# STM32G071.net
KiCad netlist of a schematic drawn in Altium Designer
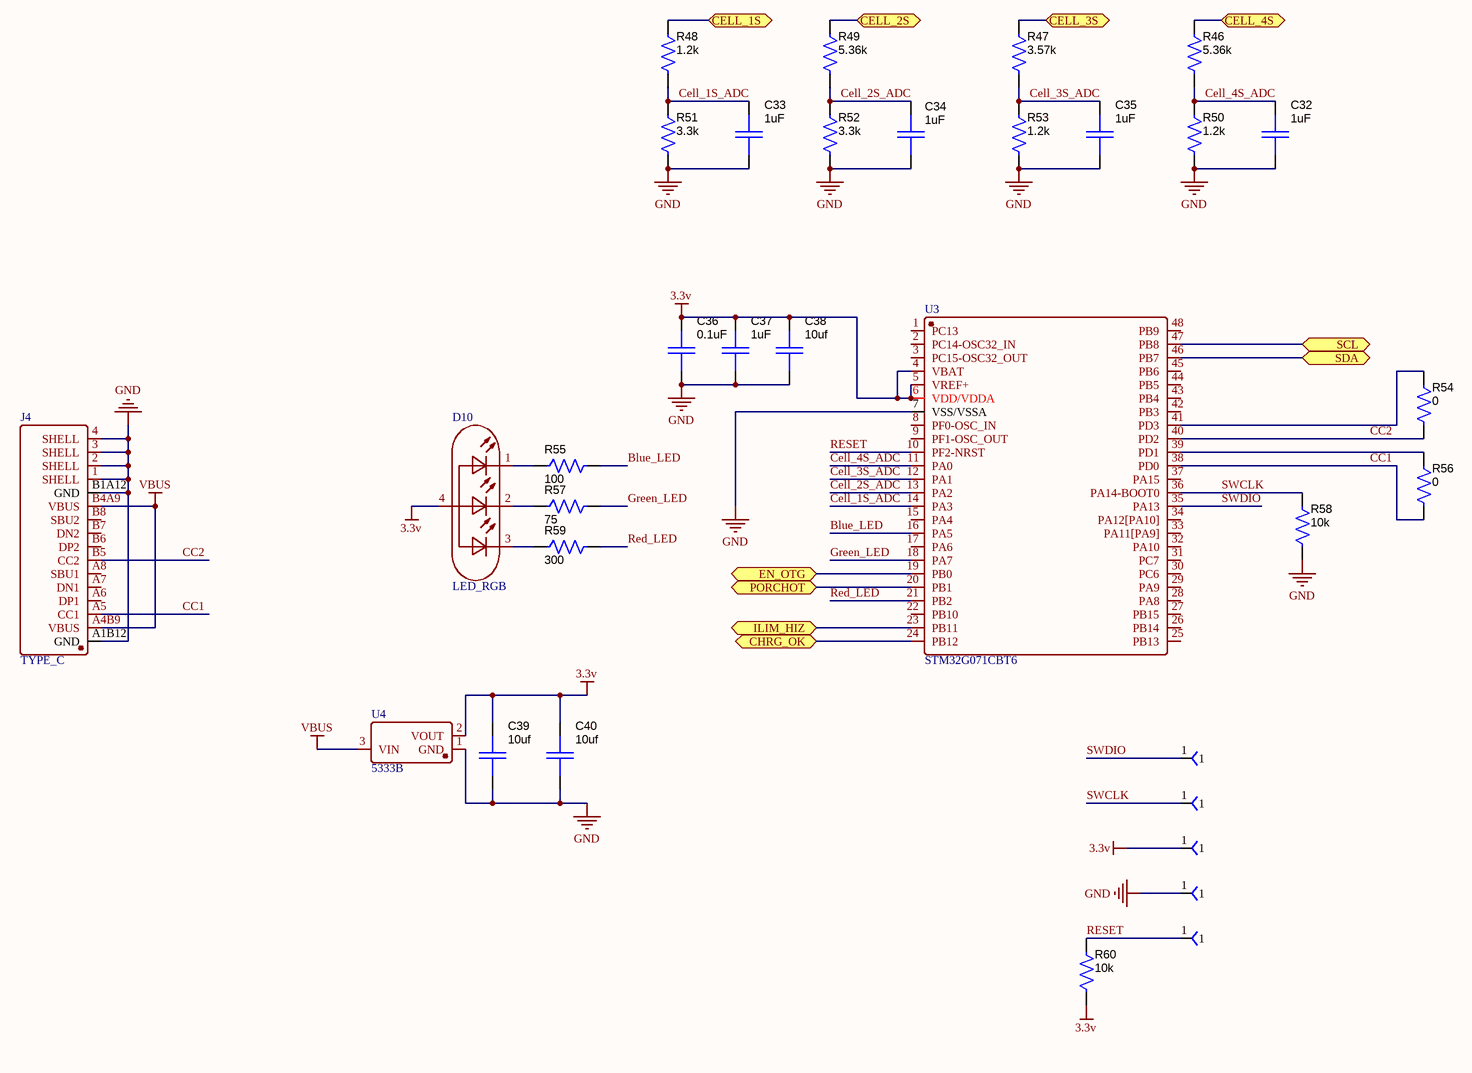
[diagram p0: STM32G071.SchDoc]

(export (version "E")
  (design (tool "Eeschema 10.0.6"))
  (components
    (comp (ref "C32")
      (value "1uF")
      (footprint "C603")
      (description "Capacitor, Ceramic Chip, 50V, X7R, ±20%")
      (fields (field (name "MANUFACTURER") "Kemet") (field (name "PARTNUMBER") "C0603C104M5RACTU"))
      (libsource (lib "BQ4050") (part "C0603"))
    )
    (comp (ref "C33")
      (value "1uF")
      (footprint "C603")
      (description "Capacitor, Ceramic Chip, 50V, X7R, ±20%")
      (fields (field (name "MANUFACTURER") "Kemet") (field (name "PARTNUMBER") "C0603C104M5RACTU"))
      (libsource (lib "BQ4050") (part "C0603"))
    )
    (comp (ref "C34")
      (value "1uF")
      (footprint "C603")
      (description "Capacitor, Ceramic Chip, 50V, X7R, ±20%")
      (fields (field (name "MANUFACTURER") "Kemet") (field (name "PARTNUMBER") "C0603C104M5RACTU"))
      (libsource (lib "BQ4050") (part "C0603"))
    )
    (comp (ref "C35")
      (value "1uF")
      (footprint "C603")
      (description "Capacitor, Ceramic Chip, 50V, X7R, ±20%")
      (fields (field (name "MANUFACTURER") "Kemet") (field (name "PARTNUMBER") "C0603C104M5RACTU"))
      (libsource (lib "BQ4050") (part "C0603"))
    )
    (comp (ref "C36")
      (value "0.1uF")
      (footprint "C603")
      (description "Capacitor, Ceramic Chip, 50V, X7R, ±20%")
      (fields (field (name "MANUFACTURER") "Kemet") (field (name "PARTNUMBER") "C0603C104M5RACTU"))
      (libsource (lib "BQ4050") (part "C0603"))
    )
    (comp (ref "C37")
      (value "1uF")
      (footprint "C603")
      (description "Capacitor, Ceramic Chip, 50V, X7R, ±20%")
      (fields (field (name "MANUFACTURER") "Kemet") (field (name "PARTNUMBER") "C0603C104M5RACTU"))
      (libsource (lib "BQ4050") (part "C0603"))
    )
    (comp (ref "C38")
      (value "10uf")
      (footprint "C603")
      (description "Capacitor, Ceramic Chip, 50V, X7R, ±20%")
      (fields (field (name "MANUFACTURER") "Kemet") (field (name "PARTNUMBER") "C0603C104M5RACTU"))
      (libsource (lib "BQ4050") (part "C0603"))
    )
    (comp (ref "C39")
      (value "10uf")
      (footprint "C603")
      (description "Capacitor, Ceramic Chip, 50V, X7R, ±20%")
      (fields (field (name "MANUFACTURER") "Kemet") (field (name "PARTNUMBER") "C0603C104M5RACTU"))
      (libsource (lib "BQ4050") (part "C0603"))
    )
    (comp (ref "C40")
      (value "10uf")
      (footprint "C603")
      (description "Capacitor, Ceramic Chip, 50V, X7R, ±20%")
      (fields (field (name "MANUFACTURER") "Kemet") (field (name "PARTNUMBER") "C0603C104M5RACTU"))
      (libsource (lib "BQ4050") (part "C0603"))
    )
    (comp (ref "D10") (value "LED_RGB") (footprint "LED_RGB") (libsource (lib "BQ4050") (part "LED_RGB")))
    (comp (ref "J4") (value "TYPE_C") (footprint "TYPE_C") (libsource (lib "BQ4050") (part "TYPE_C")))
    (comp (ref "R46")
      (value "5.36k")
      (footprint "0603")
      (description "Resistor, Chip, 1/10W, 5%")
      (fields (field (name "PARTNUMBER") "CRCW0603100RJNEAHP") (field (name "MANUFACTURER") "Vishay-Dale"))
      (libsource (lib "BQ4050") (part "R0603_1%"))
    )
    (comp (ref "R47")
      (value "3.57k")
      (footprint "0603")
      (description "Resistor, Chip, 1/10W, 5%")
      (fields (field (name "PARTNUMBER") "CRCW0603100RJNEAHP") (field (name "MANUFACTURER") "Vishay-Dale"))
      (libsource (lib "BQ4050") (part "R0603_1%"))
    )
    (comp (ref "R48")
      (value "1.2k")
      (footprint "0603")
      (description "Resistor, Chip, 1/10W, 5%")
      (fields (field (name "PARTNUMBER") "CRCW0603100RJNEAHP") (field (name "MANUFACTURER") "Vishay-Dale"))
      (libsource (lib "BQ4050") (part "R0603_1%"))
    )
    (comp (ref "R49")
      (value "5.36k")
      (footprint "0603")
      (description "Resistor, Chip, 1/10W, 5%")
      (fields (field (name "PARTNUMBER") "CRCW0603100RJNEAHP") (field (name "MANUFACTURER") "Vishay-Dale"))
      (libsource (lib "BQ4050") (part "R0603_1%"))
    )
    (comp (ref "R50")
      (value "1.2k")
      (footprint "0603")
      (description "Resistor, Chip, 1/10W, 5%")
      (fields (field (name "PARTNUMBER") "CRCW0603100RJNEAHP") (field (name "MANUFACTURER") "Vishay-Dale"))
      (libsource (lib "BQ4050") (part "R0603_1%"))
    )
    (comp (ref "R51")
      (value "3.3k")
      (footprint "0603")
      (description "Resistor, Chip, 1/10W, 5%")
      (fields (field (name "PARTNUMBER") "CRCW0603100RJNEAHP") (field (name "MANUFACTURER") "Vishay-Dale"))
      (libsource (lib "BQ4050") (part "R0603_1%"))
    )
    (comp (ref "R52")
      (value "3.3k")
      (footprint "0603")
      (description "Resistor, Chip, 1/10W, 5%")
      (fields (field (name "PARTNUMBER") "CRCW0603100RJNEAHP") (field (name "MANUFACTURER") "Vishay-Dale"))
      (libsource (lib "BQ4050") (part "R0603_1%"))
    )
    (comp (ref "R53")
      (value "1.2k")
      (footprint "0603")
      (description "Resistor, Chip, 1/10W, 5%")
      (fields (field (name "PARTNUMBER") "CRCW0603100RJNEAHP") (field (name "MANUFACTURER") "Vishay-Dale"))
      (libsource (lib "BQ4050") (part "R0603_1%"))
    )
    (comp (ref "R54")
      (value "0")
      (footprint "0603")
      (description "Resistor, Chip, 1/10W, 5%")
      (fields (field (name "PARTNUMBER") "CRCW0603100RJNEAHP") (field (name "MANUFACTURER") "Vishay-Dale"))
      (libsource (lib "BQ4050") (part "R0603_1%"))
    )
    (comp (ref "R55")
      (value "100")
      (footprint "0603")
      (description "Resistor, Chip, 1/10W, 5%")
      (fields (field (name "PARTNUMBER") "CRCW0603100RJNEAHP") (field (name "MANUFACTURER") "Vishay-Dale"))
      (libsource (lib "BQ4050") (part "R0603_1%"))
    )
    (comp (ref "R56")
      (value "0")
      (footprint "0603")
      (description "Resistor, Chip, 1/10W, 5%")
      (fields (field (name "PARTNUMBER") "CRCW0603100RJNEAHP") (field (name "MANUFACTURER") "Vishay-Dale"))
      (libsource (lib "BQ4050") (part "R0603_1%"))
    )
    (comp (ref "R57")
      (value "75")
      (footprint "0603")
      (description "Resistor, Chip, 1/10W, 5%")
      (fields (field (name "PARTNUMBER") "CRCW0603100RJNEAHP") (field (name "MANUFACTURER") "Vishay-Dale"))
      (libsource (lib "BQ4050") (part "R0603_1%"))
    )
    (comp (ref "R58")
      (value "10k")
      (footprint "0603")
      (description "Resistor, Chip, 1/10W, 5%")
      (fields (field (name "PARTNUMBER") "CRCW0603100RJNEAHP") (field (name "MANUFACTURER") "Vishay-Dale"))
      (libsource (lib "BQ4050") (part "R0603_1%"))
    )
    (comp (ref "R59")
      (value "300")
      (footprint "0603")
      (description "Resistor, Chip, 1/10W, 5%")
      (fields (field (name "PARTNUMBER") "CRCW0603100RJNEAHP") (field (name "MANUFACTURER") "Vishay-Dale"))
      (libsource (lib "BQ4050") (part "R0603_1%"))
    )
    (comp (ref "R60")
      (value "10k")
      (footprint "0603")
      (description "Resistor, Chip, 1/10W, 5%")
      (fields (field (name "PARTNUMBER") "CRCW0603100RJNEAHP") (field (name "MANUFACTURER") "Vishay-Dale"))
      (libsource (lib "BQ4050") (part "R0603_1%"))
    )
    (comp (ref "TP8")
      (value "TP_40_SMT")
      (footprint "TP_40_SMT")
      (description "Test point, 40 mil SMT")
      (fields (field (name "MANUFACTURER") "None"))
      (libsource (lib "BQ4050") (part "TP_40_SMT"))
    )
    (comp (ref "TP9")
      (value "TP_40_SMT")
      (footprint "TP_40_SMT")
      (description "Test point, 40 mil SMT")
      (fields (field (name "MANUFACTURER") "None"))
      (libsource (lib "BQ4050") (part "TP_40_SMT"))
    )
    (comp (ref "TP10")
      (value "TP_40_SMT")
      (footprint "TP_40_SMT")
      (description "Test point, 40 mil SMT")
      (fields (field (name "MANUFACTURER") "None"))
      (libsource (lib "BQ4050") (part "TP_40_SMT"))
    )
    (comp (ref "TP11")
      (value "TP_40_SMT")
      (footprint "TP_40_SMT")
      (description "Test point, 40 mil SMT")
      (fields (field (name "MANUFACTURER") "None"))
      (libsource (lib "BQ4050") (part "TP_40_SMT"))
    )
    (comp (ref "TP12")
      (value "TP_40_SMT")
      (footprint "TP_40_SMT")
      (description "Test point, 40 mil SMT")
      (fields (field (name "MANUFACTURER") "None"))
      (libsource (lib "BQ4050") (part "TP_40_SMT"))
    )
    (comp (ref "U3")
      (value "STM32G071CBT6")
      (footprint "STM32G071CBT6")
      (libsource (lib "BQ4050") (part "STM32G071CBT6"))
    )
    (comp (ref "U4")
      (value "5333B")
      (footprint "SOT-23 - duplicate")
      (libsource (lib "BQ4050") (part "5333B"))
    )
  )
  (nets
    (net (code "1") (name "/Blue_LED") (class "Default")
      (node (ref "R55") (pin "2") (pinfunction "2_2") (pintype "passive"))
      (node (ref "U3") (pin "16") (pinfunction "PA5_16") (pintype "passive"))
    )
    (net (code "2") (name "/CC1") (class "Default")
      (node (ref "J4") (pin "A5") (pinfunction "CC1_A5") (pintype "passive"))
      (node (ref "R56") (pin "2") (pinfunction "2_2") (pintype "passive"))
      (node (ref "U3") (pin "38") (pinfunction "PD0_38") (pintype "passive"))
    )
    (net (code "3") (name "/CC2") (class "Default")
      (node (ref "J4") (pin "B5") (pinfunction "CC2_B5") (pintype "passive"))
      (node (ref "R54") (pin "2") (pinfunction "2_2") (pintype "passive"))
      (node (ref "U3") (pin "40") (pinfunction "PD2_40") (pintype "passive"))
    )
    (net (code "4") (name "/CELL_1S") (class "Default")
      (node (ref "R48") (pin "1") (pinfunction "1_1") (pintype "passive"))
    )
    (net (code "5") (name "/CELL_2S") (class "Default")
      (node (ref "R49") (pin "1") (pinfunction "1_1") (pintype "passive"))
    )
    (net (code "6") (name "/CELL_3S") (class "Default")
      (node (ref "R47") (pin "1") (pinfunction "1_1") (pintype "passive"))
    )
    (net (code "7") (name "/CELL_4S") (class "Default")
      (node (ref "R46") (pin "1") (pinfunction "1_1") (pintype "passive"))
    )
    (net (code "8") (name "/CHRG_OK") (class "Default")
      (node (ref "U3") (pin "24") (pinfunction "PB12_24") (pintype "passive"))
    )
    (net (code "9") (name "/Cell_1S_ADC") (class "Default")
      (node (ref "C33") (pin "1") (pinfunction "1_1") (pintype "passive"))
      (node (ref "R48") (pin "2") (pinfunction "2_2") (pintype "passive"))
      (node (ref "R51") (pin "1") (pinfunction "1_1") (pintype "passive"))
      (node (ref "U3") (pin "14") (pinfunction "PA3_14") (pintype "passive"))
    )
    (net (code "10") (name "/Cell_2S_ADC") (class "Default")
      (node (ref "C34") (pin "1") (pinfunction "1_1") (pintype "passive"))
      (node (ref "R49") (pin "2") (pinfunction "2_2") (pintype "passive"))
      (node (ref "R52") (pin "1") (pinfunction "1_1") (pintype "passive"))
      (node (ref "U3") (pin "13") (pinfunction "PA2_13") (pintype "passive"))
    )
    (net (code "11") (name "/Cell_3S_ADC") (class "Default")
      (node (ref "C35") (pin "1") (pinfunction "1_1") (pintype "passive"))
      (node (ref "R47") (pin "2") (pinfunction "2_2") (pintype "passive"))
      (node (ref "R53") (pin "1") (pinfunction "1_1") (pintype "passive"))
      (node (ref "U3") (pin "12") (pinfunction "PA1_12") (pintype "passive"))
    )
    (net (code "12") (name "/Cell_4S_ADC") (class "Default")
      (node (ref "C32") (pin "1") (pinfunction "1_1") (pintype "passive"))
      (node (ref "R46") (pin "2") (pinfunction "2_2") (pintype "passive"))
      (node (ref "R50") (pin "1") (pinfunction "1_1") (pintype "passive"))
      (node (ref "U3") (pin "11") (pinfunction "PA0_11") (pintype "passive"))
    )
    (net (code "13") (name "/EN_OTG") (class "Default")
      (node (ref "U3") (pin "19") (pinfunction "PB0_19") (pintype "passive"))
    )
    (net (code "14") (name "/Green_LED") (class "Default")
      (node (ref "R57") (pin "2") (pinfunction "2_2") (pintype "passive"))
      (node (ref "U3") (pin "18") (pinfunction "PA7_18") (pintype "passive"))
    )
    (net (code "15") (name "/ILIM_HIZ") (class "Default")
      (node (ref "U3") (pin "23") (pinfunction "PB11_23") (pintype "passive"))
    )
    (net (code "16") (name "/PORCHOT") (class "Default")
      (node (ref "U3") (pin "20") (pinfunction "PB1_20") (pintype "passive"))
    )
    (net (code "17") (name "/RESET") (class "Default")
      (node (ref "R60") (pin "2") (pinfunction "2_2") (pintype "passive"))
      (node (ref "TP12") (pin "1") (pinfunction "1_1") (pintype "passive"))
      (node (ref "U3") (pin "10") (pinfunction "PF2-NRST_10") (pintype "passive"))
    )
    (net (code "18") (name "/Red_LED") (class "Default")
      (node (ref "R59") (pin "2") (pinfunction "2_2") (pintype "passive"))
      (node (ref "U3") (pin "21") (pinfunction "PB2_21") (pintype "passive"))
    )
    (net (code "19") (name "/SCL") (class "Default")
      (node (ref "U3") (pin "47") (pinfunction "PB8_47") (pintype "passive"))
    )
    (net (code "20") (name "/SDA") (class "Default")
      (node (ref "U3") (pin "46") (pinfunction "PB7_46") (pintype "passive"))
    )
    (net (code "21") (name "/SWCLK") (class "Default")
      (node (ref "R58") (pin "2") (pinfunction "2_2") (pintype "passive"))
      (node (ref "TP9") (pin "1") (pinfunction "1_1") (pintype "passive"))
      (node (ref "U3") (pin "36") (pinfunction "PA14-BOOT0_36") (pintype "passive"))
    )
    (net (code "22") (name "/SWDIO") (class "Default")
      (node (ref "TP8") (pin "1") (pinfunction "1_1") (pintype "passive"))
      (node (ref "U3") (pin "35") (pinfunction "PA13_35") (pintype "passive"))
    )
    (net (code "23") (name "3.3v") (class "Default")
      (node (ref "C36") (pin "1") (pinfunction "1_1") (pintype "passive"))
      (node (ref "C37") (pin "1") (pinfunction "1_1") (pintype "passive"))
      (node (ref "C38") (pin "1") (pinfunction "1_1") (pintype "passive"))
      (node (ref "C39") (pin "1") (pinfunction "1_1") (pintype "passive"))
      (node (ref "C40") (pin "1") (pinfunction "1_1") (pintype "passive"))
      (node (ref "D10") (pin "4") (pinfunction "+_4") (pintype "passive"))
      (node (ref "R60") (pin "1") (pinfunction "1_1") (pintype "passive"))
      (node (ref "TP10") (pin "1") (pinfunction "1_1") (pintype "passive"))
      (node (ref "U3") (pin "4") (pinfunction "VBAT_4") (pintype "passive"))
      (node (ref "U3") (pin "5") (pinfunction "VREF+_5") (pintype "passive"))
      (node (ref "U3") (pin "6") (pinfunction "VDD/VDDA_6") (pintype "passive"))
      (node (ref "U4") (pin "2") (pinfunction "VOUT_2") (pintype "passive"))
    )
    (net (code "24") (name "GND") (class "Default")
      (node (ref "C32") (pin "2") (pinfunction "2_2") (pintype "passive"))
      (node (ref "C33") (pin "2") (pinfunction "2_2") (pintype "passive"))
      (node (ref "C34") (pin "2") (pinfunction "2_2") (pintype "passive"))
      (node (ref "C35") (pin "2") (pinfunction "2_2") (pintype "passive"))
      (node (ref "C36") (pin "2") (pinfunction "2_2") (pintype "passive"))
      (node (ref "C37") (pin "2") (pinfunction "2_2") (pintype "passive"))
      (node (ref "C38") (pin "2") (pinfunction "2_2") (pintype "passive"))
      (node (ref "C39") (pin "2") (pinfunction "2_2") (pintype "passive"))
      (node (ref "C40") (pin "2") (pinfunction "2_2") (pintype "passive"))
      (node (ref "J4") (pin "1") (pinfunction "SHELL_1") (pintype "passive"))
      (node (ref "J4") (pin "2") (pinfunction "SHELL_2") (pintype "passive"))
      (node (ref "J4") (pin "3") (pinfunction "SHELL_3") (pintype "passive"))
      (node (ref "J4") (pin "4") (pinfunction "SHELL_4") (pintype "passive"))
      (node (ref "J4") (pin "A1B12") (pinfunction "GND_A1B12") (pintype "passive"))
      (node (ref "J4") (pin "B1A12") (pinfunction "GND_B1A12") (pintype "passive"))
      (node (ref "R50") (pin "2") (pinfunction "2_2") (pintype "passive"))
      (node (ref "R51") (pin "2") (pinfunction "2_2") (pintype "passive"))
      (node (ref "R52") (pin "2") (pinfunction "2_2") (pintype "passive"))
      (node (ref "R53") (pin "2") (pinfunction "2_2") (pintype "passive"))
      (node (ref "R58") (pin "1") (pinfunction "1_1") (pintype "passive"))
      (node (ref "TP11") (pin "1") (pinfunction "1_1") (pintype "passive"))
      (node (ref "U3") (pin "7") (pinfunction "VSS/VSSA_7") (pintype "passive"))
      (node (ref "U4") (pin "1") (pinfunction "GND_1") (pintype "passive"))
    )
    (net (code "25") (name "Net-(D10-B-)") (class "Default")
      (node (ref "D10") (pin "3") (pinfunction "B-_3") (pintype "passive"))
      (node (ref "R59") (pin "1") (pinfunction "1_1") (pintype "passive"))
    )
    (net (code "26") (name "Net-(D10-G-)") (class "Default")
      (node (ref "D10") (pin "2") (pinfunction "G-_2") (pintype "passive"))
      (node (ref "R57") (pin "1") (pinfunction "1_1") (pintype "passive"))
    )
    (net (code "27") (name "Net-(D10-R-)") (class "Default")
      (node (ref "D10") (pin "1") (pinfunction "R-_1") (pintype "passive"))
      (node (ref "R55") (pin "1") (pinfunction "1_1") (pintype "passive"))
    )
    (net (code "28") (name "Net-(U3-PD1)") (class "Default")
      (node (ref "R56") (pin "1") (pinfunction "1_1") (pintype "passive"))
      (node (ref "U3") (pin "39") (pinfunction "PD1_39") (pintype "passive"))
    )
    (net (code "29") (name "Net-(U3-PD3)") (class "Default")
      (node (ref "R54") (pin "1") (pinfunction "1_1") (pintype "passive"))
      (node (ref "U3") (pin "41") (pinfunction "PD3_41") (pintype "passive"))
    )
    (net (code "30") (name "VBUS") (class "Default")
      (node (ref "J4") (pin "A4B9") (pinfunction "VBUS_A4B9") (pintype "passive"))
      (node (ref "J4") (pin "B4A9") (pinfunction "VBUS_B4A9") (pintype "passive"))
      (node (ref "U4") (pin "3") (pinfunction "VIN_3") (pintype "passive"))
    )
    (net (code "31") (name "unconnected-(J4-DN1-PadA7)") (class "Default")
      (node (ref "J4") (pin "A7") (pinfunction "DN1_A7") (pintype "passive"))
    )
    (net (code "32") (name "unconnected-(J4-DN2-PadB7)") (class "Default")
      (node (ref "J4") (pin "B7") (pinfunction "DN2_B7") (pintype "passive"))
    )
    (net (code "33") (name "unconnected-(J4-DP1-PadA6)") (class "Default")
      (node (ref "J4") (pin "A6") (pinfunction "DP1_A6") (pintype "passive"))
    )
    (net (code "34") (name "unconnected-(J4-DP2-PadB6)") (class "Default")
      (node (ref "J4") (pin "B6") (pinfunction "DP2_B6") (pintype "passive"))
    )
    (net (code "35") (name "unconnected-(J4-SBU1-PadA8)") (class "Default")
      (node (ref "J4") (pin "A8") (pinfunction "SBU1_A8") (pintype "passive"))
    )
    (net (code "36") (name "unconnected-(J4-SBU2-PadB8)") (class "Default")
      (node (ref "J4") (pin "B8") (pinfunction "SBU2_B8") (pintype "passive"))
    )
    (net (code "37") (name "unconnected-(U3-PA4-Pad15)") (class "Default")
      (node (ref "U3") (pin "15") (pinfunction "PA4_15") (pintype "passive"))
    )
    (net (code "38") (name "unconnected-(U3-PA6-Pad17)") (class "Default")
      (node (ref "U3") (pin "17") (pinfunction "PA6_17") (pintype "passive"))
    )
    (net (code "39") (name "unconnected-(U3-PA8-Pad28)") (class "Default")
      (node (ref "U3") (pin "28") (pinfunction "PA8_28") (pintype "passive"))
    )
    (net (code "40") (name "unconnected-(U3-PA9-Pad29)") (class "Default")
      (node (ref "U3") (pin "29") (pinfunction "PA9_29") (pintype "passive"))
    )
    (net (code "41") (name "unconnected-(U3-PA10-Pad32)") (class "Default")
      (node (ref "U3") (pin "32") (pinfunction "PA10_32") (pintype "passive"))
    )
    (net (code "42") (name "unconnected-(U3-PA11[PA9]-Pad33)") (class "Default")
      (node (ref "U3") (pin "33") (pinfunction "PA11[PA9]_33") (pintype "passive"))
    )
    (net (code "43") (name "unconnected-(U3-PA12[PA10]-Pad34)") (class "Default")
      (node (ref "U3") (pin "34") (pinfunction "PA12[PA10]_34") (pintype "passive"))
    )
    (net (code "44") (name "unconnected-(U3-PA15-Pad37)") (class "Default")
      (node (ref "U3") (pin "37") (pinfunction "PA15_37") (pintype "passive"))
    )
    (net (code "45") (name "unconnected-(U3-PB3-Pad42)") (class "Default")
      (node (ref "U3") (pin "42") (pinfunction "PB3_42") (pintype "passive"))
    )
    (net (code "46") (name "unconnected-(U3-PB4-Pad43)") (class "Default")
      (node (ref "U3") (pin "43") (pinfunction "PB4_43") (pintype "passive"))
    )
    (net (code "47") (name "unconnected-(U3-PB5-Pad44)") (class "Default")
      (node (ref "U3") (pin "44") (pinfunction "PB5_44") (pintype "passive"))
    )
    (net (code "48") (name "unconnected-(U3-PB6-Pad45)") (class "Default")
      (node (ref "U3") (pin "45") (pinfunction "PB6_45") (pintype "passive"))
    )
    (net (code "49") (name "unconnected-(U3-PB9-Pad48)") (class "Default")
      (node (ref "U3") (pin "48") (pinfunction "PB9_48") (pintype "passive"))
    )
    (net (code "50") (name "unconnected-(U3-PB10-Pad22)") (class "Default")
      (node (ref "U3") (pin "22") (pinfunction "PB10_22") (pintype "passive"))
    )
    (net (code "51") (name "unconnected-(U3-PB13-Pad25)") (class "Default")
      (node (ref "U3") (pin "25") (pinfunction "PB13_25") (pintype "passive"))
    )
    (net (code "52") (name "unconnected-(U3-PB14-Pad26)") (class "Default")
      (node (ref "U3") (pin "26") (pinfunction "PB14_26") (pintype "passive"))
    )
    (net (code "53") (name "unconnected-(U3-PB15-Pad27)") (class "Default")
      (node (ref "U3") (pin "27") (pinfunction "PB15_27") (pintype "passive"))
    )
    (net (code "54") (name "unconnected-(U3-PC6-Pad30)") (class "Default")
      (node (ref "U3") (pin "30") (pinfunction "PC6_30") (pintype "passive"))
    )
    (net (code "55") (name "unconnected-(U3-PC7-Pad31)") (class "Default")
      (node (ref "U3") (pin "31") (pinfunction "PC7_31") (pintype "passive"))
    )
    (net (code "56") (name "unconnected-(U3-PC13-Pad1)") (class "Default")
      (node (ref "U3") (pin "1") (pinfunction "PC13_1") (pintype "passive"))
    )
    (net (code "57") (name "unconnected-(U3-PC14-OSC32_IN-Pad2)") (class "Default")
      (node (ref "U3") (pin "2") (pinfunction "PC14-OSC32_IN_2") (pintype "passive"))
    )
    (net (code "58") (name "unconnected-(U3-PC15-OSC32_OUT-Pad3)") (class "Default")
      (node (ref "U3") (pin "3") (pinfunction "PC15-OSC32_OUT_3") (pintype "passive"))
    )
    (net (code "59") (name "unconnected-(U3-PF0-OSC_IN-Pad8)") (class "Default")
      (node (ref "U3") (pin "8") (pinfunction "PF0-OSC_IN_8") (pintype "passive"))
    )
    (net (code "60") (name "unconnected-(U3-PF1-OSC_OUT-Pad9)") (class "Default")
      (node (ref "U3") (pin "9") (pinfunction "PF1-OSC_OUT_9") (pintype "passive"))
    )
  )
)
